# BaseSheet.net
KiCad netlist of a schematic drawn in Altium Designer
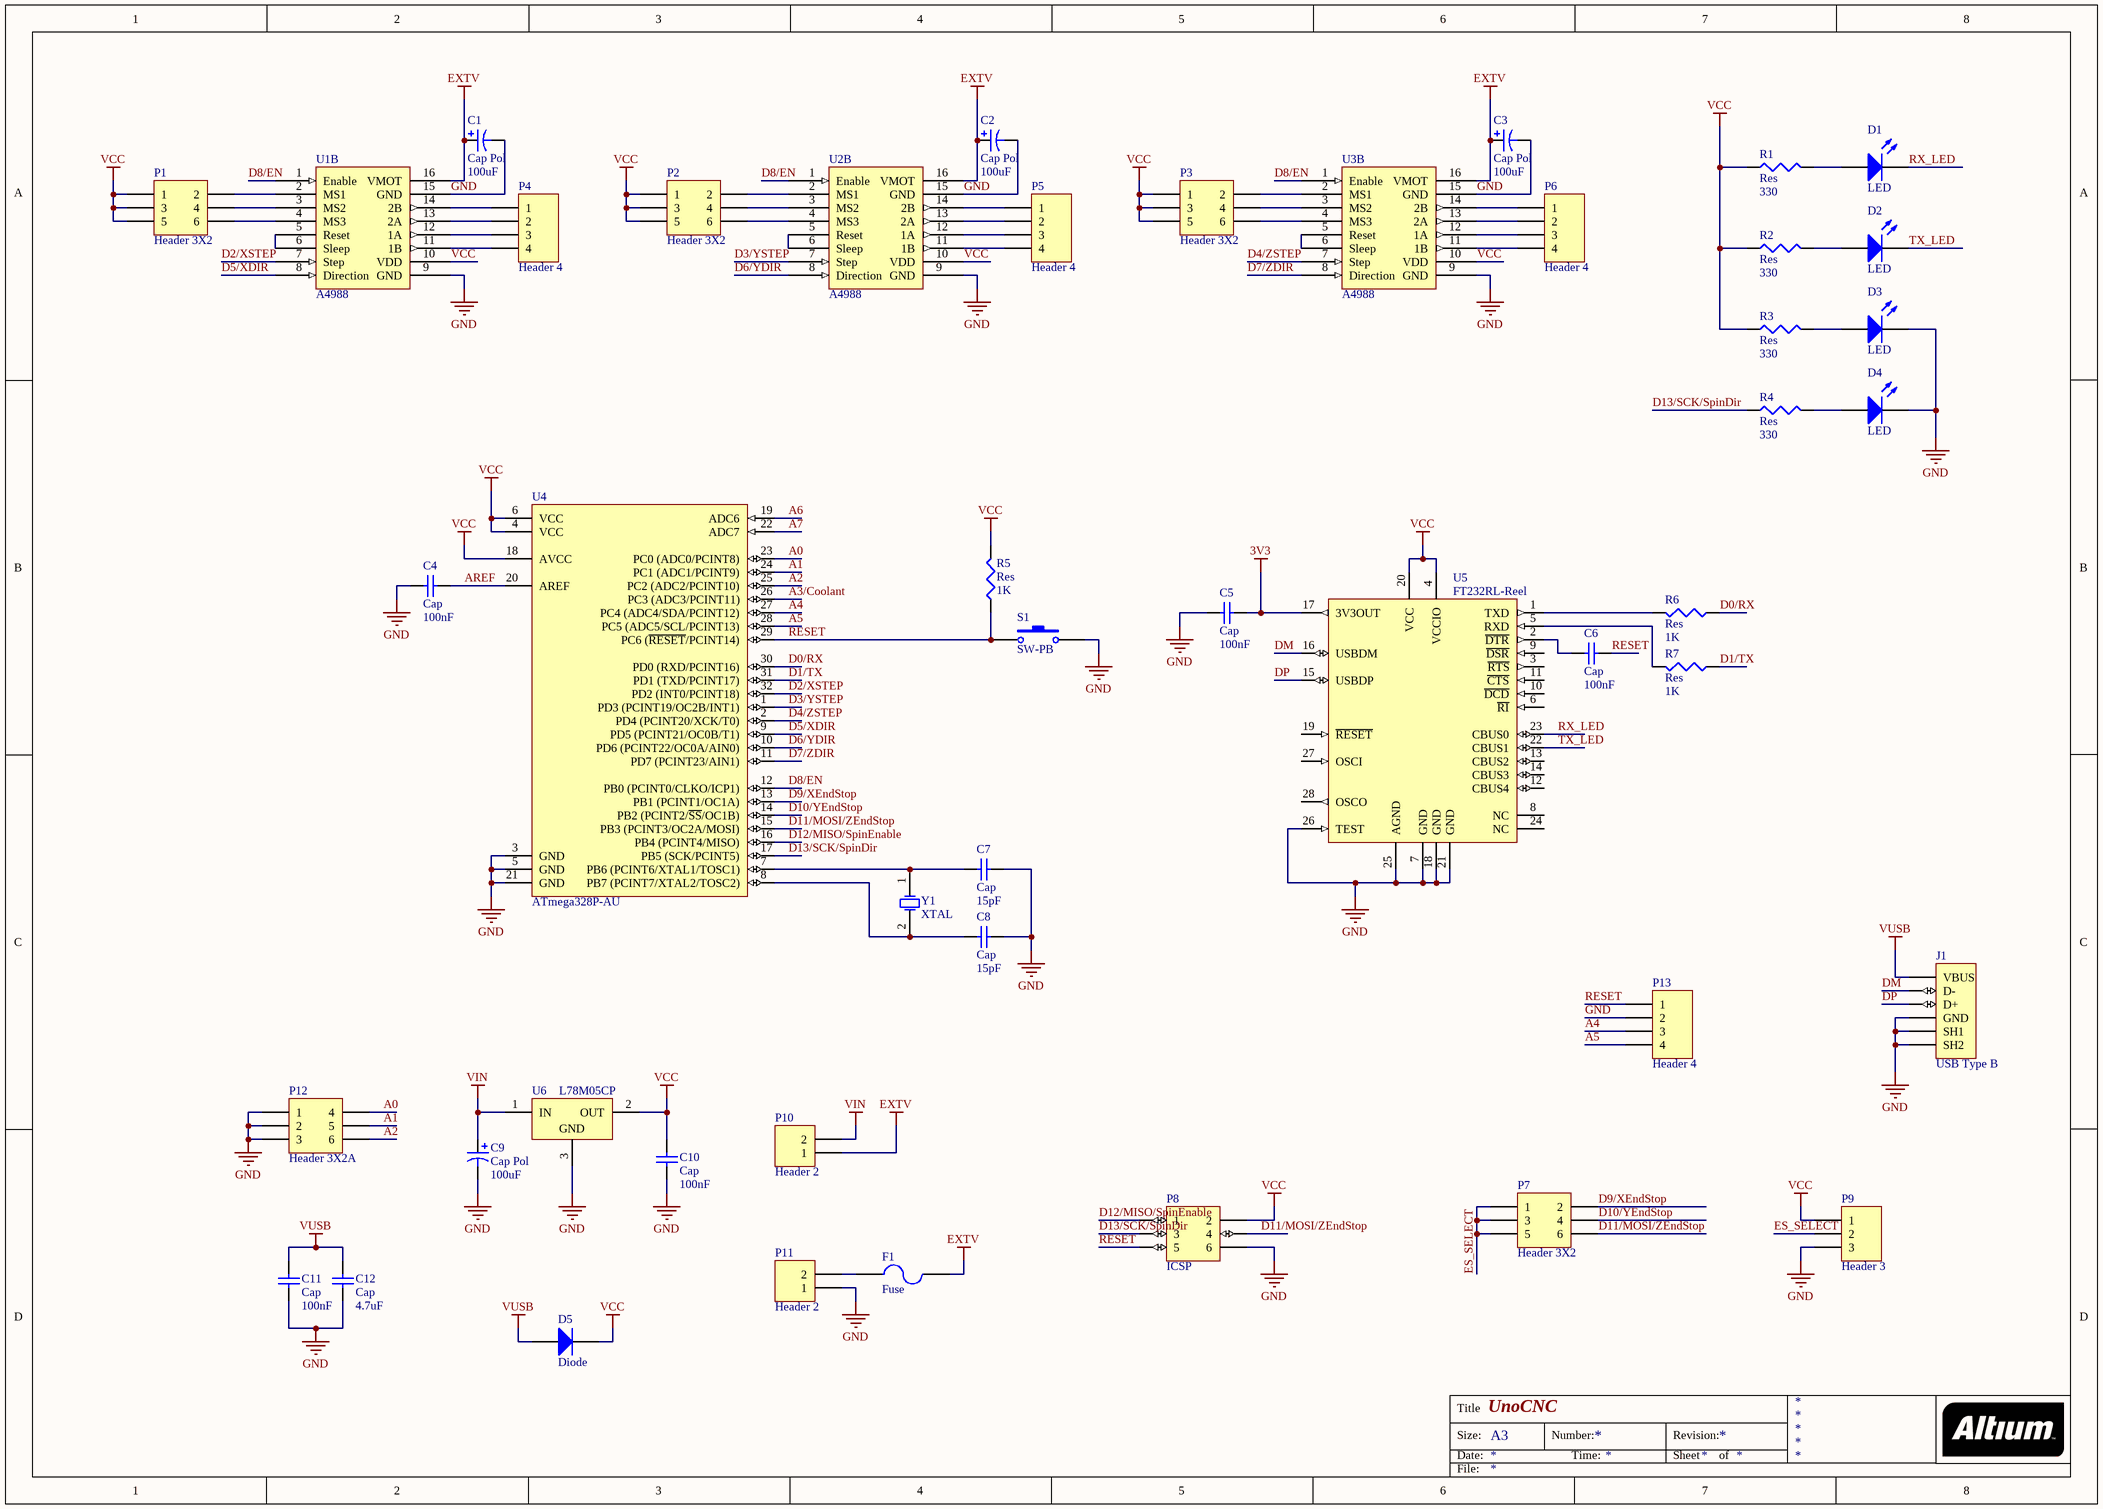
[diagram p0: BaseSheet.SchDoc]

(export (version "E")
  (design (tool "Eeschema 10.0.6"))
  (components
    (comp (ref "C1")
      (value "Cap Pol")
      (footprint "Capacitor Polar Radial Cylinder:CAPPR2.5-6.3x6.8/H.9")
      (description "Polarized Capacitor (Radial)")
      (fields (field (name "ALTIUM_VALUE") "100uF") (field (name "PUBLISHER") "Altium Limited"))
      (libsource (lib "Miscellaneous Devices") (part "Cap Pol1"))
    )
    (comp (ref "C2")
      (value "Cap Pol")
      (footprint "CAPPR2.5-6.3x6.8/H.9")
      (description "Polarized Capacitor (Radial)")
      (fields (field (name "ALTIUM_VALUE") "100uF") (field (name "PUBLISHER") "Altium Limited"))
      (libsource (lib "Miscellaneous Devices") (part "Cap Pol1"))
    )
    (comp (ref "C3")
      (value "Cap Pol")
      (footprint "CAPPR2.5-6.3x6.8/H.9")
      (description "Polarized Capacitor (Radial)")
      (fields (field (name "ALTIUM_VALUE") "100uF") (field (name "PUBLISHER") "Altium Limited"))
      (libsource (lib "Miscellaneous Devices") (part "Cap Pol1"))
    )
    (comp (ref "C4")
      (value "Cap")
      (footprint "C1206")
      (description "Capacitor (Semiconductor SIM Model)")
      (fields (field (name "ALTIUM_VALUE") "100nF") (field (name "PUBLISHER") "Altium Limited"))
      (libsource (lib "Miscellaneous Devices") (part "Cap Semi"))
    )
    (comp (ref "C5")
      (value "Cap")
      (footprint "C1206")
      (description "Capacitor (Semiconductor SIM Model)")
      (fields (field (name "ALTIUM_VALUE") "100nF") (field (name "PUBLISHER") "Altium Limited"))
      (libsource (lib "Miscellaneous Devices") (part "Cap Semi"))
    )
    (comp (ref "C6")
      (value "Cap")
      (footprint "C1206")
      (description "Capacitor (Semiconductor SIM Model)")
      (fields (field (name "ALTIUM_VALUE") "100nF") (field (name "PUBLISHER") "Altium Limited"))
      (libsource (lib "Miscellaneous Devices") (part "Cap Semi"))
    )
    (comp (ref "C7")
      (value "Cap")
      (footprint "C1206")
      (description "Capacitor (Semiconductor SIM Model)")
      (fields (field (name "ALTIUM_VALUE") "15pF") (field (name "PUBLISHER") "Altium Limited"))
      (libsource (lib "Miscellaneous Devices") (part "Cap Semi"))
    )
    (comp (ref "C8")
      (value "Cap")
      (footprint "C1206")
      (description "Capacitor (Semiconductor SIM Model)")
      (fields (field (name "ALTIUM_VALUE") "15pF") (field (name "PUBLISHER") "Altium Limited"))
      (libsource (lib "Miscellaneous Devices") (part "Cap Semi"))
    )
    (comp (ref "C9")
      (value "Cap Pol")
      (footprint "CAPPR2.5-6.3x6.8/H.9")
      (description "Polarized Capacitor (Radial)")
      (fields (field (name "ALTIUM_VALUE") "100uF") (field (name "PUBLISHER") "Altium Limited"))
      (libsource (lib "Miscellaneous Devices") (part "Cap Pol1"))
    )
    (comp (ref "C10")
      (value "Cap")
      (footprint "C1206")
      (description "Capacitor (Semiconductor SIM Model)")
      (fields (field (name "ALTIUM_VALUE") "100nF") (field (name "PUBLISHER") "Altium Limited"))
      (libsource (lib "Miscellaneous Devices") (part "Cap Semi"))
    )
    (comp (ref "C11")
      (value "Cap")
      (footprint "C1206")
      (description "Capacitor (Semiconductor SIM Model)")
      (fields (field (name "ALTIUM_VALUE") "100nF") (field (name "PUBLISHER") "Altium Limited"))
      (libsource (lib "Miscellaneous Devices") (part "Cap Semi"))
    )
    (comp (ref "C12")
      (value "Cap")
      (footprint "C1206")
      (description "Capacitor (Semiconductor SIM Model)")
      (fields (field (name "ALTIUM_VALUE") "4.7uF") (field (name "PUBLISHER") "Altium Limited"))
      (libsource (lib "Miscellaneous Devices") (part "Cap Semi"))
    )
    (comp (ref "D1")
      (value "LED")
      (footprint "Miscellaneous Devices:6-0805_L")
      (description "Typical BLUE SiC LED")
      (fields (field (name "PUBLISHER") "Altium Limited"))
      (libsource (lib "Miscellaneous Devices") (part "LED3"))
    )
    (comp (ref "D2")
      (value "LED")
      (footprint "6-0805_L")
      (description "Typical BLUE SiC LED")
      (fields (field (name "PUBLISHER") "Altium Limited"))
      (libsource (lib "Miscellaneous Devices") (part "LED3"))
    )
    (comp (ref "D3")
      (value "LED")
      (footprint "6-0805_L")
      (description "Typical BLUE SiC LED")
      (fields (field (name "PUBLISHER") "Altium Limited"))
      (libsource (lib "Miscellaneous Devices") (part "LED3"))
    )
    (comp (ref "D4")
      (value "LED")
      (footprint "6-0805_L")
      (description "Typical BLUE SiC LED")
      (fields (field (name "PUBLISHER") "Altium Limited"))
      (libsource (lib "Miscellaneous Devices") (part "LED3"))
    )
    (comp (ref "D5")
      (value "Diode")
      (footprint "DSO-C2/X2.3")
      (description "Default Diode")
      (fields (field (name "PUBLISHER") "Altium Limited"))
      (libsource (lib "Miscellaneous Devices") (part "Diode"))
    )
    (comp (ref "F1")
      (value "Fuse")
      (footprint "Fuse:BLX-A")
      (fields (field (name "PUBLISHER") "Altium Limited"))
      (libsource (lib "Miscellaneous Devices") (part "Fuse 2"))
    )
    (comp (ref "J1")
      (value "USB Type B")
      (footprint "USB2.5-2H4D")
      (description "Header, 6-Pin")
      (fields (field (name "PUBLISHER") "Altium Limited"))
      (libsource (lib "Miscellaneous Connectors") (part "Header 6"))
    )
    (comp (ref "P1")
      (value "Header 3X2")
      (footprint "HDR2X3")
      (description "Header, 3-Pin, Dual row")
      (fields (field (name "PUBLISHER") "Altium Limited"))
      (libsource (lib "Miscellaneous Connectors") (part "Header 3X2"))
    )
    (comp (ref "P2")
      (value "Header 3X2")
      (footprint "HDR2X3")
      (description "Header, 3-Pin, Dual row")
      (fields (field (name "PUBLISHER") "Altium Limited"))
      (libsource (lib "Miscellaneous Connectors") (part "Header 3X2"))
    )
    (comp (ref "P3")
      (value "Header 3X2")
      (footprint "HDR2X3")
      (description "Header, 3-Pin, Dual row")
      (fields (field (name "PUBLISHER") "Altium Limited"))
      (libsource (lib "Miscellaneous Connectors") (part "Header 3X2"))
    )
    (comp (ref "P4")
      (value "Header 4")
      (footprint "HDR1X4")
      (description "Header, 4-Pin")
      (fields (field (name "PUBLISHER") "Altium Limited"))
      (libsource (lib "Miscellaneous Connectors") (part "Header 4"))
    )
    (comp (ref "P5")
      (value "Header 4")
      (footprint "HDR1X4")
      (description "Header, 4-Pin")
      (fields (field (name "PUBLISHER") "Altium Limited"))
      (libsource (lib "Miscellaneous Connectors") (part "Header 4"))
    )
    (comp (ref "P6")
      (value "Header 4")
      (footprint "HDR1X4")
      (description "Header, 4-Pin")
      (fields (field (name "PUBLISHER") "Altium Limited"))
      (libsource (lib "Miscellaneous Connectors") (part "Header 4"))
    )
    (comp (ref "P7")
      (value "Header 3X2")
      (footprint "HDR2X3")
      (description "Header, 3-Pin, Dual row")
      (fields (field (name "PUBLISHER") "Altium Limited"))
      (libsource (lib "Miscellaneous Connectors") (part "Header 3X2"))
    )
    (comp (ref "P8")
      (value "ICSP")
      (footprint "HDR2X3")
      (description "Header, 3-Pin, Dual row")
      (fields (field (name "PUBLISHER") "Altium Limited"))
      (libsource (lib "Miscellaneous Connectors") (part "Header 3X2"))
    )
    (comp (ref "P9")
      (value "Header 3")
      (footprint "HDR1X3")
      (description "Header, 3-Pin")
      (fields (field (name "PUBLISHER") "Altium Limited"))
      (libsource (lib "Miscellaneous Connectors") (part "Header 3"))
    )
    (comp (ref "P10")
      (value "Header 2")
      (footprint "HDR1X2")
      (description "Header, 2-Pin")
      (fields (field (name "PUBLISHER") "Altium Limited"))
      (libsource (lib "Miscellaneous Connectors") (part "Header 2"))
    )
    (comp (ref "P11")
      (value "Header 2")
      (footprint "Phoenix Con 2pin:2Pin Phoenix Contact")
      (description "Header, 2-Pin")
      (fields (field (name "PUBLISHER") "Altium Limited"))
      (libsource (lib "Miscellaneous Connectors") (part "Header 2"))
    )
    (comp (ref "P12")
      (value "Header 3X2A")
      (footprint "HDR2X3_CEN")
      (description "Header, 3-Pin, Dual row")
      (fields (field (name "PUBLISHER") "Altium Limited"))
      (libsource (lib "Miscellaneous Connectors") (part "Header 3X2A"))
    )
    (comp (ref "P13")
      (value "Header 4")
      (footprint "HDR1X4")
      (description "Header, 4-Pin")
      (fields (field (name "PUBLISHER") "Altium Limited"))
      (libsource (lib "Miscellaneous Connectors") (part "Header 4"))
    )
    (comp (ref "R1")
      (value "Res")
      (footprint "J1-0603")
      (description "Resistor")
      (fields (field (name "ALTIUM_VALUE") "330") (field (name "PUBLISHER") "Altium Limited"))
      (libsource (lib "Miscellaneous Devices") (part "Res3"))
    )
    (comp (ref "R2")
      (value "Res")
      (footprint "J1-0603")
      (description "Resistor")
      (fields (field (name "ALTIUM_VALUE") "330") (field (name "PUBLISHER") "Altium Limited"))
      (libsource (lib "Miscellaneous Devices") (part "Res3"))
    )
    (comp (ref "R3")
      (value "Res")
      (footprint "J1-0603")
      (description "Resistor")
      (fields (field (name "ALTIUM_VALUE") "330") (field (name "PUBLISHER") "Altium Limited"))
      (libsource (lib "Miscellaneous Devices") (part "Res3"))
    )
    (comp (ref "R4")
      (value "Res")
      (footprint "J1-0603")
      (description "Resistor")
      (fields (field (name "ALTIUM_VALUE") "330") (field (name "PUBLISHER") "Altium Limited"))
      (libsource (lib "Miscellaneous Devices") (part "Res3"))
    )
    (comp (ref "R5")
      (value "Res")
      (footprint "J1-0603")
      (description "Resistor")
      (fields (field (name "ALTIUM_VALUE") "1K") (field (name "PUBLISHER") "Altium Limited"))
      (libsource (lib "Miscellaneous Devices") (part "Res3"))
    )
    (comp (ref "R6")
      (value "Res")
      (footprint "J1-0603")
      (description "Resistor")
      (fields (field (name "ALTIUM_VALUE") "1K") (field (name "PUBLISHER") "Altium Limited"))
      (libsource (lib "Miscellaneous Devices") (part "Res3"))
    )
    (comp (ref "R7")
      (value "Res")
      (footprint "J1-0603")
      (description "Resistor")
      (fields (field (name "ALTIUM_VALUE") "1K") (field (name "PUBLISHER") "Altium Limited"))
      (libsource (lib "Miscellaneous Devices") (part "Res3"))
    )
    (comp (ref "S1")
      (value "SW-PB")
      (footprint "SPST-2")
      (description "Switch")
      (fields (field (name "PUBLISHER") "Altium Limited"))
      (libsource (lib "Miscellaneous Devices") (part "SW-PB"))
    )
    (comp (ref "U1")
      (value "A4988")
      (footprint "A4988:DIP16")
      (description "Stepper Motor Driver")
      (libsource (lib "A4988") (part "A4988"))
    )
    (comp (ref "U2")
      (value "A4988")
      (footprint "A4988:DIP16")
      (description "Stepper Motor Driver")
      (libsource (lib "A4988") (part "A4988"))
    )
    (comp (ref "U3")
      (value "A4988")
      (footprint "A4988:DIP16")
      (description "Stepper Motor Driver")
      (libsource (lib "A4988") (part "A4988"))
    )
    (comp (ref "U4")
      (value "ATmega328P-AU")
      (footprint "32A_N")
      (fields (field (name "PUBLISHER") "Altium Limited"))
      (libsource (lib "Atmel Microcontroller 8-Bit megaAVR") (part "ATmega328P-AU"))
    )
    (comp (ref "U5")
      (value "FT232RL-Reel")
      (footprint "SSOP-28_N")
      (description "USB UART Asynchronous Serial Data Transfer Chip, 28-pin SSOP, Tape and Reel")
      (fields (field (name "MANUFACTURER") "FTDI"))
      (libsource (lib "FTDI FT Series") (part "FT232RL-Reel"))
    )
    (comp (ref "U6")
      (value "L78M05CP")
      (footprint "ISOWATT220AB")
      (description "Positive Voltage Regulator")
      (fields (field (name "PUBLISHER") "Altium Limited"))
      (libsource (lib "ST Power Mgt Voltage Regulator") (part "L78M05CP"))
    )
    (comp (ref "Y1")
      (value "XTAL")
      (footprint "Crystal Oscillator:BCY-W2/E4.7")
      (description "Crystal Oscillator")
      (fields (field (name "PUBLISHER") "Altium Limited"))
      (libsource (lib "Miscellaneous Devices") (part "XTAL"))
    )
  )
  (nets
    (net (code "1") (name "/A0") (class "Default")
      (node (ref "P12") (pin "4") (pinfunction "4_4") (pintype "passive"))
      (node (ref "U4") (pin "23") (pinfunction "PC0_(ADC0/PCINT8)_23") (pintype "bidirectional"))
    )
    (net (code "2") (name "/A1") (class "Default")
      (node (ref "P12") (pin "5") (pinfunction "5_5") (pintype "passive"))
      (node (ref "U4") (pin "24") (pinfunction "PC1_(ADC1/PCINT9)_24") (pintype "bidirectional"))
    )
    (net (code "3") (name "/A2") (class "Default")
      (node (ref "P12") (pin "6") (pinfunction "6_6") (pintype "passive"))
      (node (ref "U4") (pin "25") (pinfunction "PC2_(ADC2/PCINT10)_25") (pintype "bidirectional"))
    )
    (net (code "4") (name "/A3{slash}Coolant") (class "Default")
      (node (ref "U4") (pin "26") (pinfunction "PC3_(ADC3/PCINT11)_26") (pintype "bidirectional"))
    )
    (net (code "5") (name "/A4") (class "Default")
      (node (ref "P13") (pin "3") (pinfunction "3_3") (pintype "passive"))
      (node (ref "U4") (pin "27") (pinfunction "PC4_(ADC4/SDA/PCINT12)_27") (pintype "bidirectional"))
    )
    (net (code "6") (name "/A5") (class "Default")
      (node (ref "P13") (pin "4") (pinfunction "4_4") (pintype "passive"))
      (node (ref "U4") (pin "28") (pinfunction "PC5_(ADC5/SCL/PCINT13)_28") (pintype "bidirectional"))
    )
    (net (code "7") (name "/A6") (class "Default")
      (node (ref "U4") (pin "19") (pinfunction "ADC6_19") (pintype "input"))
    )
    (net (code "8") (name "/A7") (class "Default")
      (node (ref "U4") (pin "22") (pinfunction "ADC7_22") (pintype "input"))
    )
    (net (code "9") (name "/AREF") (class "Default")
      (node (ref "C4") (pin "2") (pinfunction "2_2") (pintype "passive"))
      (node (ref "U4") (pin "20") (pinfunction "AREF_20") (pintype "passive"))
    )
    (net (code "10") (name "/D0{slash}RX") (class "Default")
      (node (ref "R6") (pin "1") (pinfunction "1_1") (pintype "passive"))
      (node (ref "U4") (pin "30") (pinfunction "PD0_(RXD/PCINT16)_30") (pintype "bidirectional"))
    )
    (net (code "11") (name "/D1{slash}TX") (class "Default")
      (node (ref "R7") (pin "1") (pinfunction "1_1") (pintype "passive"))
      (node (ref "U4") (pin "31") (pinfunction "PD1_(TXD/PCINT17)_31") (pintype "bidirectional"))
    )
    (net (code "12") (name "/D2{slash}XSTEP") (class "Default")
      (node (ref "U1") (pin "7") (pinfunction "Step_7") (pintype "input"))
      (node (ref "U4") (pin "32") (pinfunction "PD2_(INT0/PCINT18)_32") (pintype "bidirectional"))
    )
    (net (code "13") (name "/D3{slash}YSTEP") (class "Default")
      (node (ref "U2") (pin "7") (pinfunction "Step_7") (pintype "input"))
      (node (ref "U4") (pin "1") (pinfunction "PD3_(PCINT19/OC2B/INT1)_1") (pintype "bidirectional"))
    )
    (net (code "14") (name "/D4{slash}ZSTEP") (class "Default")
      (node (ref "U3") (pin "7") (pinfunction "Step_7") (pintype "input"))
      (node (ref "U4") (pin "2") (pinfunction "PD4_(PCINT20/XCK/T0)_2") (pintype "bidirectional"))
    )
    (net (code "15") (name "/D5{slash}XDIR") (class "Default")
      (node (ref "U1") (pin "8") (pinfunction "Direction_8") (pintype "input"))
      (node (ref "U4") (pin "9") (pinfunction "PD5_(PCINT21/OC0B/T1)_9") (pintype "bidirectional"))
    )
    (net (code "16") (name "/D6{slash}YDIR") (class "Default")
      (node (ref "U2") (pin "8") (pinfunction "Direction_8") (pintype "input"))
      (node (ref "U4") (pin "10") (pinfunction "PD6_(PCINT22/OC0A/AIN0)_10") (pintype "bidirectional"))
    )
    (net (code "17") (name "/D7{slash}ZDIR") (class "Default")
      (node (ref "U3") (pin "8") (pinfunction "Direction_8") (pintype "input"))
      (node (ref "U4") (pin "11") (pinfunction "PD7_(PCINT23/AIN1)_11") (pintype "bidirectional"))
    )
    (net (code "18") (name "/D8{slash}EN") (class "Default")
      (node (ref "U1") (pin "1") (pinfunction "Enable_1") (pintype "input"))
      (node (ref "U2") (pin "1") (pinfunction "Enable_1") (pintype "input"))
      (node (ref "U3") (pin "1") (pinfunction "Enable_1") (pintype "input"))
      (node (ref "U4") (pin "12") (pinfunction "PB0_(PCINT0/CLKO/ICP1)_12") (pintype "bidirectional"))
    )
    (net (code "19") (name "/D9{slash}XEndStop") (class "Default")
      (node (ref "P7") (pin "2") (pinfunction "2_2") (pintype "passive"))
      (node (ref "U4") (pin "13") (pinfunction "PB1_(PCINT1/OC1A)_13") (pintype "bidirectional"))
    )
    (net (code "20") (name "/D10{slash}YEndStop") (class "Default")
      (node (ref "P7") (pin "4") (pinfunction "4_4") (pintype "passive"))
      (node (ref "U4") (pin "14") (pinfunction "PB2_(PCINT2/~{SS}/OC1B)_14") (pintype "bidirectional"))
    )
    (net (code "21") (name "/D11{slash}MOSI{slash}ZEndStop") (class "Default")
      (node (ref "P7") (pin "6") (pinfunction "6_6") (pintype "passive"))
      (node (ref "P8") (pin "4") (pinfunction "4_4") (pintype "passive"))
      (node (ref "U4") (pin "15") (pinfunction "PB3_(PCINT3/OC2A/MOSI)_15") (pintype "bidirectional"))
    )
    (net (code "22") (name "/D12{slash}MISO{slash}SpinEnable") (class "Default")
      (node (ref "P8") (pin "1") (pinfunction "1_1") (pintype "passive"))
      (node (ref "U4") (pin "16") (pinfunction "PB4_(PCINT4/MISO)_16") (pintype "bidirectional"))
    )
    (net (code "23") (name "/D13{slash}SCK{slash}SpinDir") (class "Default")
      (node (ref "P8") (pin "3") (pinfunction "3_3") (pintype "passive"))
      (node (ref "R4") (pin "1") (pinfunction "1_1") (pintype "passive"))
      (node (ref "U4") (pin "17") (pinfunction "PB5_(SCK/PCINT5)_17") (pintype "bidirectional"))
    )
    (net (code "24") (name "/DM") (class "Default")
      (node (ref "J1") (pin "2") (pinfunction "D-_2") (pintype "bidirectional"))
      (node (ref "U5") (pin "16") (pinfunction "USBDM_16") (pintype "bidirectional"))
    )
    (net (code "25") (name "/DP") (class "Default")
      (node (ref "J1") (pin "3") (pinfunction "D+_3") (pintype "bidirectional"))
      (node (ref "U5") (pin "15") (pinfunction "USBDP_15") (pintype "bidirectional"))
    )
    (net (code "26") (name "/ES_SELECT") (class "Default")
      (node (ref "P7") (pin "1") (pinfunction "1_1") (pintype "passive"))
      (node (ref "P7") (pin "3") (pinfunction "3_3") (pintype "passive"))
      (node (ref "P7") (pin "5") (pinfunction "5_5") (pintype "passive"))
      (node (ref "P9") (pin "2") (pinfunction "2_2") (pintype "passive"))
    )
    (net (code "27") (name "/RESET") (class "Default")
      (node (ref "C6") (pin "2") (pinfunction "2_2") (pintype "passive"))
      (node (ref "P13") (pin "1") (pinfunction "1_1") (pintype "passive"))
      (node (ref "P8") (pin "5") (pinfunction "5_5") (pintype "passive"))
      (node (ref "R5") (pin "1") (pinfunction "1_1") (pintype "passive"))
      (node (ref "S1") (pin "1") (pinfunction "1_1") (pintype "passive"))
      (node (ref "U4") (pin "29") (pinfunction "PC6_(~{RESET}/PCINT14)_29") (pintype "bidirectional"))
    )
    (net (code "28") (name "/RX_LED") (class "Default")
      (node (ref "D1") (pin "2") (pinfunction "K_2") (pintype "passive"))
      (node (ref "U5") (pin "23") (pinfunction "CBUS0_23") (pintype "bidirectional"))
    )
    (net (code "29") (name "/TX_LED") (class "Default")
      (node (ref "D2") (pin "2") (pinfunction "K_2") (pintype "passive"))
      (node (ref "U5") (pin "22") (pinfunction "CBUS1_22") (pintype "bidirectional"))
    )
    (net (code "30") (name "3V3") (class "Default")
      (node (ref "C5") (pin "2") (pinfunction "2_2") (pintype "passive"))
      (node (ref "U5") (pin "17") (pinfunction "3V3OUT_17") (pintype "output"))
    )
    (net (code "31") (name "EXTV") (class "Default")
      (node (ref "C1") (pin "1") (pinfunction "1_1") (pintype "passive"))
      (node (ref "C2") (pin "1") (pinfunction "1_1") (pintype "passive"))
      (node (ref "C3") (pin "1") (pinfunction "1_1") (pintype "passive"))
      (node (ref "F1") (pin "2") (pinfunction "2_2") (pintype "passive"))
      (node (ref "P10") (pin "1") (pinfunction "1_1") (pintype "passive"))
      (node (ref "U1") (pin "16") (pinfunction "VMOT_16") (pintype "power_in"))
      (node (ref "U2") (pin "16") (pinfunction "VMOT_16") (pintype "power_in"))
      (node (ref "U3") (pin "16") (pinfunction "VMOT_16") (pintype "power_in"))
    )
    (net (code "32") (name "GND") (class "Default")
      (node (ref "C1") (pin "2") (pinfunction "2_2") (pintype "passive"))
      (node (ref "C10") (pin "1") (pinfunction "1_1") (pintype "passive"))
      (node (ref "C11") (pin "1") (pinfunction "1_1") (pintype "passive"))
      (node (ref "C12") (pin "1") (pinfunction "1_1") (pintype "passive"))
      (node (ref "C2") (pin "2") (pinfunction "2_2") (pintype "passive"))
      (node (ref "C3") (pin "2") (pinfunction "2_2") (pintype "passive"))
      (node (ref "C4") (pin "1") (pinfunction "1_1") (pintype "passive"))
      (node (ref "C5") (pin "1") (pinfunction "1_1") (pintype "passive"))
      (node (ref "C7") (pin "2") (pinfunction "2_2") (pintype "passive"))
      (node (ref "C8") (pin "2") (pinfunction "2_2") (pintype "passive"))
      (node (ref "C9") (pin "2") (pinfunction "2_2") (pintype "passive"))
      (node (ref "D3") (pin "2") (pinfunction "K_2") (pintype "passive"))
      (node (ref "D4") (pin "2") (pinfunction "K_2") (pintype "passive"))
      (node (ref "J1") (pin "4") (pinfunction "GND_4") (pintype "power_in"))
      (node (ref "J1") (pin "5") (pinfunction "SH1_5") (pintype "power_in"))
      (node (ref "J1") (pin "6") (pinfunction "SH2_6") (pintype "power_in"))
      (node (ref "P11") (pin "1") (pinfunction "1_1") (pintype "passive"))
      (node (ref "P12") (pin "1") (pinfunction "1_1") (pintype "passive"))
      (node (ref "P12") (pin "2") (pinfunction "2_2") (pintype "passive"))
      (node (ref "P12") (pin "3") (pinfunction "3_3") (pintype "passive"))
      (node (ref "P13") (pin "2") (pinfunction "2_2") (pintype "passive"))
      (node (ref "P8") (pin "6") (pinfunction "6_6") (pintype "passive"))
      (node (ref "P9") (pin "3") (pinfunction "3_3") (pintype "passive"))
      (node (ref "S1") (pin "2") (pinfunction "2_2") (pintype "passive"))
      (node (ref "U1") (pin "15") (pinfunction "GND_15") (pintype "power_in"))
      (node (ref "U1") (pin "9") (pinfunction "GND_9") (pintype "power_in"))
      (node (ref "U2") (pin "15") (pinfunction "GND_15") (pintype "power_in"))
      (node (ref "U2") (pin "9") (pinfunction "GND_9") (pintype "power_in"))
      (node (ref "U3") (pin "15") (pinfunction "GND_15") (pintype "power_in"))
      (node (ref "U3") (pin "9") (pinfunction "GND_9") (pintype "power_in"))
      (node (ref "U4") (pin "21") (pinfunction "GND_21") (pintype "power_in"))
      (node (ref "U4") (pin "3") (pinfunction "GND_3") (pintype "power_in"))
      (node (ref "U4") (pin "5") (pinfunction "GND_5") (pintype "power_in"))
      (node (ref "U5") (pin "18") (pinfunction "GND_18") (pintype "power_in"))
      (node (ref "U5") (pin "21") (pinfunction "GND_21") (pintype "power_in"))
      (node (ref "U5") (pin "25") (pinfunction "AGND_25") (pintype "power_in"))
      (node (ref "U5") (pin "26") (pinfunction "TEST_26") (pintype "input"))
      (node (ref "U5") (pin "7") (pinfunction "GND_7") (pintype "power_in"))
      (node (ref "U6") (pin "3") (pinfunction "GND_3") (pintype "power_in"))
    )
    (net (code "33") (name "Net-(D1-A)") (class "Default")
      (node (ref "D1") (pin "1") (pinfunction "A_1") (pintype "passive"))
      (node (ref "R1") (pin "2") (pinfunction "2_2") (pintype "passive"))
    )
    (net (code "34") (name "Net-(D2-A)") (class "Default")
      (node (ref "D2") (pin "1") (pinfunction "A_1") (pintype "passive"))
      (node (ref "R2") (pin "2") (pinfunction "2_2") (pintype "passive"))
    )
    (net (code "35") (name "Net-(D3-A)") (class "Default")
      (node (ref "D3") (pin "1") (pinfunction "A_1") (pintype "passive"))
      (node (ref "R3") (pin "2") (pinfunction "2_2") (pintype "passive"))
    )
    (net (code "36") (name "Net-(D4-A)") (class "Default")
      (node (ref "D4") (pin "1") (pinfunction "A_1") (pintype "passive"))
      (node (ref "R4") (pin "2") (pinfunction "2_2") (pintype "passive"))
    )
    (net (code "37") (name "Net-(F1-Pad1)") (class "Default")
      (node (ref "F1") (pin "1") (pinfunction "1_1") (pintype "passive"))
      (node (ref "P11") (pin "2") (pinfunction "2_2") (pintype "passive"))
    )
    (net (code "38") (name "Net-(U1B-1A)") (class "Default")
      (node (ref "P4") (pin "3") (pinfunction "3_3") (pintype "passive"))
      (node (ref "U1") (pin "12") (pinfunction "1A_12") (pintype "output"))
    )
    (net (code "39") (name "Net-(U1B-1B)") (class "Default")
      (node (ref "P4") (pin "4") (pinfunction "4_4") (pintype "passive"))
      (node (ref "U1") (pin "11") (pinfunction "1B_11") (pintype "output"))
    )
    (net (code "40") (name "Net-(U1B-2A)") (class "Default")
      (node (ref "P4") (pin "2") (pinfunction "2_2") (pintype "passive"))
      (node (ref "U1") (pin "13") (pinfunction "2A_13") (pintype "output"))
    )
    (net (code "41") (name "Net-(U1B-2B)") (class "Default")
      (node (ref "P4") (pin "1") (pinfunction "1_1") (pintype "passive"))
      (node (ref "U1") (pin "14") (pinfunction "2B_14") (pintype "output"))
    )
    (net (code "42") (name "Net-(U1B-MS1)") (class "Default")
      (node (ref "P1") (pin "2") (pinfunction "2_2") (pintype "passive"))
      (node (ref "U1") (pin "2") (pinfunction "MS1_2") (pintype "passive"))
    )
    (net (code "43") (name "Net-(U1B-MS2)") (class "Default")
      (node (ref "P1") (pin "4") (pinfunction "4_4") (pintype "passive"))
      (node (ref "U1") (pin "3") (pinfunction "MS2_3") (pintype "passive"))
    )
    (net (code "44") (name "Net-(U1B-MS3)") (class "Default")
      (node (ref "P1") (pin "6") (pinfunction "6_6") (pintype "passive"))
      (node (ref "U1") (pin "4") (pinfunction "MS3_4") (pintype "passive"))
    )
    (net (code "45") (name "Net-(U1B-Reset)") (class "Default")
      (node (ref "U1") (pin "5") (pinfunction "Reset_5") (pintype "passive"))
      (node (ref "U1") (pin "6") (pinfunction "Sleep_6") (pintype "passive"))
    )
    (net (code "46") (name "Net-(U2B-1A)") (class "Default")
      (node (ref "P5") (pin "3") (pinfunction "3_3") (pintype "passive"))
      (node (ref "U2") (pin "12") (pinfunction "1A_12") (pintype "output"))
    )
    (net (code "47") (name "Net-(U2B-1B)") (class "Default")
      (node (ref "P5") (pin "4") (pinfunction "4_4") (pintype "passive"))
      (node (ref "U2") (pin "11") (pinfunction "1B_11") (pintype "output"))
    )
    (net (code "48") (name "Net-(U2B-2A)") (class "Default")
      (node (ref "P5") (pin "2") (pinfunction "2_2") (pintype "passive"))
      (node (ref "U2") (pin "13") (pinfunction "2A_13") (pintype "output"))
    )
    (net (code "49") (name "Net-(U2B-2B)") (class "Default")
      (node (ref "P5") (pin "1") (pinfunction "1_1") (pintype "passive"))
      (node (ref "U2") (pin "14") (pinfunction "2B_14") (pintype "output"))
    )
    (net (code "50") (name "Net-(U2B-MS1)") (class "Default")
      (node (ref "P2") (pin "2") (pinfunction "2_2") (pintype "passive"))
      (node (ref "U2") (pin "2") (pinfunction "MS1_2") (pintype "passive"))
    )
    (net (code "51") (name "Net-(U2B-MS2)") (class "Default")
      (node (ref "P2") (pin "4") (pinfunction "4_4") (pintype "passive"))
      (node (ref "U2") (pin "3") (pinfunction "MS2_3") (pintype "passive"))
    )
    (net (code "52") (name "Net-(U2B-MS3)") (class "Default")
      (node (ref "P2") (pin "6") (pinfunction "6_6") (pintype "passive"))
      (node (ref "U2") (pin "4") (pinfunction "MS3_4") (pintype "passive"))
    )
    (net (code "53") (name "Net-(U2B-Reset)") (class "Default")
      (node (ref "U2") (pin "5") (pinfunction "Reset_5") (pintype "passive"))
      (node (ref "U2") (pin "6") (pinfunction "Sleep_6") (pintype "passive"))
    )
    (net (code "54") (name "Net-(U3B-1A)") (class "Default")
      (node (ref "P6") (pin "3") (pinfunction "3_3") (pintype "passive"))
      (node (ref "U3") (pin "12") (pinfunction "1A_12") (pintype "output"))
    )
    (net (code "55") (name "Net-(U3B-1B)") (class "Default")
      (node (ref "P6") (pin "4") (pinfunction "4_4") (pintype "passive"))
      (node (ref "U3") (pin "11") (pinfunction "1B_11") (pintype "output"))
    )
    (net (code "56") (name "Net-(U3B-2A)") (class "Default")
      (node (ref "P6") (pin "2") (pinfunction "2_2") (pintype "passive"))
      (node (ref "U3") (pin "13") (pinfunction "2A_13") (pintype "output"))
    )
    (net (code "57") (name "Net-(U3B-2B)") (class "Default")
      (node (ref "P6") (pin "1") (pinfunction "1_1") (pintype "passive"))
      (node (ref "U3") (pin "14") (pinfunction "2B_14") (pintype "output"))
    )
    (net (code "58") (name "Net-(U3B-MS1)") (class "Default")
      (node (ref "P3") (pin "2") (pinfunction "2_2") (pintype "passive"))
      (node (ref "U3") (pin "2") (pinfunction "MS1_2") (pintype "passive"))
    )
    (net (code "59") (name "Net-(U3B-MS2)") (class "Default")
      (node (ref "P3") (pin "4") (pinfunction "4_4") (pintype "passive"))
      (node (ref "U3") (pin "3") (pinfunction "MS2_3") (pintype "passive"))
    )
    (net (code "60") (name "Net-(U3B-MS3)") (class "Default")
      (node (ref "P3") (pin "6") (pinfunction "6_6") (pintype "passive"))
      (node (ref "U3") (pin "4") (pinfunction "MS3_4") (pintype "passive"))
    )
    (net (code "61") (name "Net-(U3B-Reset)") (class "Default")
      (node (ref "U3") (pin "5") (pinfunction "Reset_5") (pintype "passive"))
      (node (ref "U3") (pin "6") (pinfunction "Sleep_6") (pintype "passive"))
    )
    (net (code "62") (name "Net-(U4-PB6_(PCINT6{slash}XTAL1{slash}TOSC1))") (class "Default")
      (node (ref "C7") (pin "1") (pinfunction "1_1") (pintype "passive"))
      (node (ref "U4") (pin "7") (pinfunction "PB6_(PCINT6/XTAL1/TOSC1)_7") (pintype "bidirectional"))
      (node (ref "Y1") (pin "1") (pinfunction "OSC1_1") (pintype "passive"))
    )
    (net (code "63") (name "Net-(U4-PB7_(PCINT7{slash}XTAL2{slash}TOSC2))") (class "Default")
      (node (ref "C8") (pin "1") (pinfunction "1_1") (pintype "passive"))
      (node (ref "U4") (pin "8") (pinfunction "PB7_(PCINT7/XTAL2/TOSC2)_8") (pintype "bidirectional"))
      (node (ref "Y1") (pin "2") (pinfunction "OSC2_2") (pintype "passive"))
    )
    (net (code "64") (name "Net-(U5-RXD)") (class "Default")
      (node (ref "R7") (pin "2") (pinfunction "2_2") (pintype "passive"))
      (node (ref "U5") (pin "5") (pinfunction "RXD_5") (pintype "input"))
    )
    (net (code "65") (name "Net-(U5-TXD)") (class "Default")
      (node (ref "R6") (pin "2") (pinfunction "2_2") (pintype "passive"))
      (node (ref "U5") (pin "1") (pinfunction "TXD_1") (pintype "output"))
    )
    (net (code "66") (name "Net-(U5-~{DTR})") (class "Default")
      (node (ref "C6") (pin "1") (pinfunction "1_1") (pintype "passive"))
      (node (ref "U5") (pin "2") (pinfunction "~{DTR}_2") (pintype "output"))
    )
    (net (code "67") (name "VCC") (class "Default")
      (node (ref "C10") (pin "2") (pinfunction "2_2") (pintype "passive"))
      (node (ref "D5") (pin "2") (pinfunction "K_2") (pintype "passive"))
      (node (ref "P1") (pin "1") (pinfunction "1_1") (pintype "passive"))
      (node (ref "P1") (pin "3") (pinfunction "3_3") (pintype "passive"))
      (node (ref "P1") (pin "5") (pinfunction "5_5") (pintype "passive"))
      (node (ref "P2") (pin "1") (pinfunction "1_1") (pintype "passive"))
      (node (ref "P2") (pin "3") (pinfunction "3_3") (pintype "passive"))
      (node (ref "P2") (pin "5") (pinfunction "5_5") (pintype "passive"))
      (node (ref "P3") (pin "1") (pinfunction "1_1") (pintype "passive"))
      (node (ref "P3") (pin "3") (pinfunction "3_3") (pintype "passive"))
      (node (ref "P3") (pin "5") (pinfunction "5_5") (pintype "passive"))
      (node (ref "P8") (pin "2") (pinfunction "2_2") (pintype "passive"))
      (node (ref "P9") (pin "1") (pinfunction "1_1") (pintype "passive"))
      (node (ref "R1") (pin "1") (pinfunction "1_1") (pintype "passive"))
      (node (ref "R2") (pin "1") (pinfunction "1_1") (pintype "passive"))
      (node (ref "R3") (pin "1") (pinfunction "1_1") (pintype "passive"))
      (node (ref "R5") (pin "2") (pinfunction "2_2") (pintype "passive"))
      (node (ref "U1") (pin "10") (pinfunction "VDD_10") (pintype "power_in"))
      (node (ref "U2") (pin "10") (pinfunction "VDD_10") (pintype "power_in"))
      (node (ref "U3") (pin "10") (pinfunction "VDD_10") (pintype "power_in"))
      (node (ref "U4") (pin "18") (pinfunction "AVCC_18") (pintype "power_in"))
      (node (ref "U4") (pin "4") (pinfunction "VCC_4") (pintype "power_in"))
      (node (ref "U4") (pin "6") (pinfunction "VCC_6") (pintype "power_in"))
      (node (ref "U5") (pin "20") (pinfunction "VCC_20") (pintype "power_in"))
      (node (ref "U5") (pin "4") (pinfunction "VCCIO_4") (pintype "power_in"))
      (node (ref "U6") (pin "2") (pinfunction "OUT_2") (pintype "power_in"))
    )
    (net (code "68") (name "VIN") (class "Default")
      (node (ref "C9") (pin "1") (pinfunction "1_1") (pintype "passive"))
      (node (ref "P10") (pin "2") (pinfunction "2_2") (pintype "passive"))
      (node (ref "U6") (pin "1") (pinfunction "IN_1") (pintype "power_in"))
    )
    (net (code "69") (name "VUSB") (class "Default")
      (node (ref "C11") (pin "2") (pinfunction "2_2") (pintype "passive"))
      (node (ref "C12") (pin "2") (pinfunction "2_2") (pintype "passive"))
      (node (ref "D5") (pin "1") (pinfunction "A_1") (pintype "passive"))
      (node (ref "J1") (pin "1") (pinfunction "VBUS_1") (pintype "power_in"))
    )
    (net (code "70") (name "unconnected-(U5-CBUS2-Pad13)") (class "Default")
      (node (ref "U5") (pin "13") (pinfunction "CBUS2_13") (pintype "bidirectional"))
    )
    (net (code "71") (name "unconnected-(U5-CBUS3-Pad14)") (class "Default")
      (node (ref "U5") (pin "14") (pinfunction "CBUS3_14") (pintype "bidirectional"))
    )
    (net (code "72") (name "unconnected-(U5-CBUS4-Pad12)") (class "Default")
      (node (ref "U5") (pin "12") (pinfunction "CBUS4_12") (pintype "bidirectional"))
    )
    (net (code "73") (name "unconnected-(U5-NC-Pad8)") (class "Default")
      (node (ref "U5") (pin "8") (pinfunction "NC_8") (pintype "passive"))
    )
    (net (code "74") (name "unconnected-(U5-NC-Pad24)") (class "Default")
      (node (ref "U5") (pin "24") (pinfunction "NC_24") (pintype "passive"))
    )
    (net (code "75") (name "unconnected-(U5-OSCI-Pad27)") (class "Default")
      (node (ref "U5") (pin "27") (pinfunction "OSCI_27") (pintype "input"))
    )
    (net (code "76") (name "unconnected-(U5-OSCO-Pad28)") (class "Default")
      (node (ref "U5") (pin "28") (pinfunction "OSCO_28") (pintype "output"))
    )
    (net (code "77") (name "unconnected-(U5-~{CTS}-Pad11)") (class "Default")
      (node (ref "U5") (pin "11") (pinfunction "~{CTS}_11") (pintype "input"))
    )
    (net (code "78") (name "unconnected-(U5-~{DCD}-Pad10)") (class "Default")
      (node (ref "U5") (pin "10") (pinfunction "~{DCD}_10") (pintype "input"))
    )
    (net (code "79") (name "unconnected-(U5-~{DSR}-Pad9)") (class "Default")
      (node (ref "U5") (pin "9") (pinfunction "~{DSR}_9") (pintype "input"))
    )
    (net (code "80") (name "unconnected-(U5-~{RESET}-Pad19)") (class "Default")
      (node (ref "U5") (pin "19") (pinfunction "~{RESET}_19") (pintype "input"))
    )
    (net (code "81") (name "unconnected-(U5-~{RI}-Pad6)") (class "Default")
      (node (ref "U5") (pin "6") (pinfunction "~{RI}_6") (pintype "input"))
    )
    (net (code "82") (name "unconnected-(U5-~{RTS}-Pad3)") (class "Default")
      (node (ref "U5") (pin "3") (pinfunction "~{RTS}_3") (pintype "output"))
    )
  )
)
